# ATS_Unit.net
KiCad netlist of a schematic drawn in Altium Designer
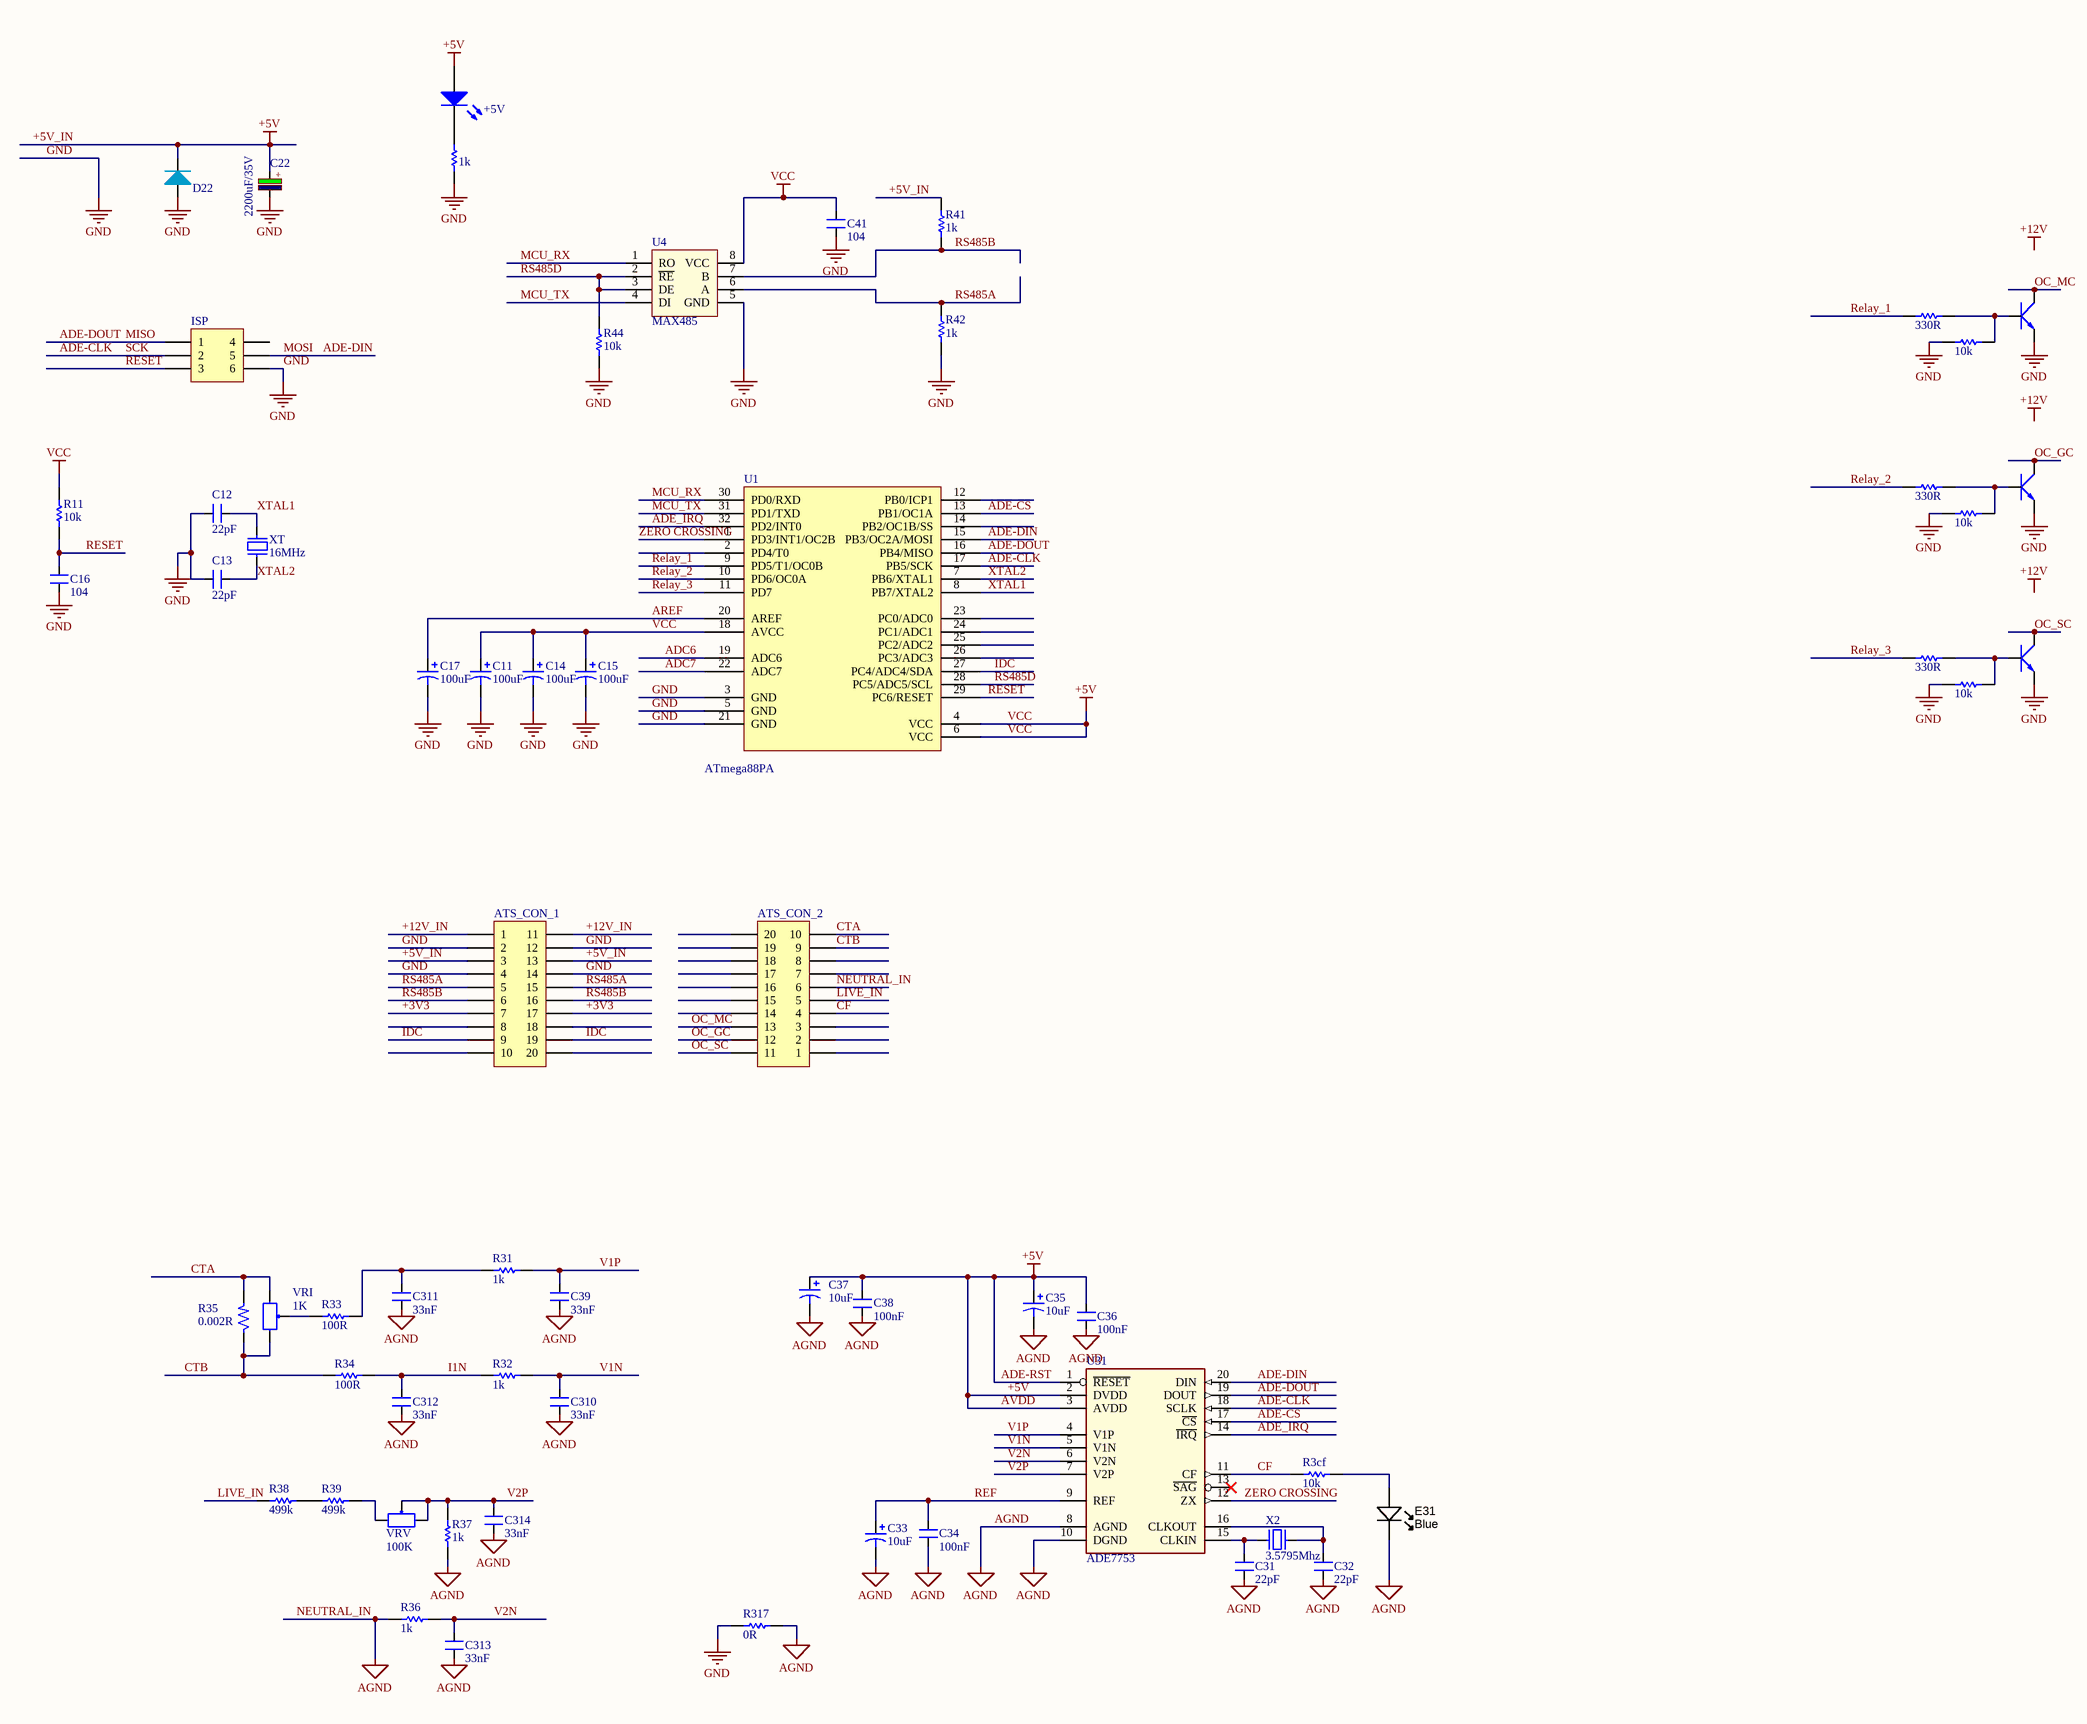
[diagram p0: ATS_Unit.SchDoc]

(export (version "E")
  (design (tool "Eeschema 10.0.6"))
  (components
    (comp (ref "+5V") (value "Led") (footprint "LED 5mm RED") (libsource (lib "Tuan") (part "Led")))
    (comp (ref "ATS_CON_1")
      (value "Header 10X2A")
      (footprint "OMC10")
      (description "Header, 10-Pin, Dual row")
      (fields (field (name "PUBLISHER") "Altium Limited"))
      (libsource (lib "Miscellaneous Connectors") (part "Header 10X2A"))
    )
    (comp (ref "ATS_CON_2")
      (value "Header 10X2A")
      (footprint "OMC10")
      (description "Header, 10-Pin, Dual row")
      (fields (field (name "PUBLISHER") "Altium Limited"))
      (libsource (lib "") (part "Header 10X2A_1"))
    )
    (comp (ref "C11")
      (value "100uF")
      (footprint "CAPC2012N_F")
      (fields (field (name "Comment") "Cap"))
      (libsource (lib "Tuan") (part "Cap"))
    )
    (comp (ref "C12")
      (value "22pF")
      (footprint "CAPC1608N")
      (fields (field (name "Comment") "CAP NP"))
      (libsource (lib "Tuan") (part "CAP NP"))
    )
    (comp (ref "C13")
      (value "22pF")
      (footprint "CAPC1608N")
      (fields (field (name "Comment") "CAP NP"))
      (libsource (lib "Tuan") (part "CAP NP"))
    )
    (comp (ref "C14")
      (value "100uF")
      (footprint "CAPC2012N_F")
      (fields (field (name "Comment") "Cap"))
      (libsource (lib "Tuan") (part "Cap"))
    )
    (comp (ref "C15")
      (value "100uF")
      (footprint "CAPC2012N_F")
      (fields (field (name "Comment") "Cap"))
      (libsource (lib "Tuan") (part "Cap"))
    )
    (comp (ref "C16")
      (value "104")
      (footprint "CAPC1608N")
      (fields (field (name "Comment") "CAP NP"))
      (libsource (lib "Tuan") (part "CAP NP"))
    )
    (comp (ref "C17")
      (value "100uF")
      (footprint "CAPC2012N_F")
      (fields (field (name "Comment") "Cap"))
      (libsource (lib "Tuan") (part "Cap"))
    )
    (comp (ref "C22")
      (value "2200uF/35V")
      (footprint "PBL - SMD Packages:CAP_ELEC_SIZE_G")
      (description "Cap 1000uF/16V - 220uF/50V")
      (libsource (lib "heromap") (part "CP4"))
    )
    (comp (ref "C31")
      (value "22pF")
      (footprint "CAPC1608N")
      (fields (field (name "Comment") "CAP NP"))
      (libsource (lib "ELS-PLC-2.0") (part "CAP NP"))
    )
    (comp (ref "C32")
      (value "22pF")
      (footprint "CAPC1608N")
      (fields (field (name "Comment") "CAP NP"))
      (libsource (lib "ELS-PLC-2.0") (part "CAP NP"))
    )
    (comp (ref "C33")
      (value "10uF")
      (footprint "CAPC2012N_F")
      (fields (field (name "Comment") "Cap"))
      (libsource (lib "Tuan") (part "Cap"))
    )
    (comp (ref "C34")
      (value "100nF")
      (footprint "CAPC1608N")
      (fields (field (name "Comment") "CAP NP"))
      (libsource (lib "ELS-PLC-2.0") (part "CAP NP"))
    )
    (comp (ref "C35")
      (value "10uF")
      (footprint "CAPC2012N_F")
      (fields (field (name "Comment") "Cap"))
      (libsource (lib "Tuan") (part "Cap"))
    )
    (comp (ref "C36")
      (value "100nF")
      (footprint "CAPC1608N")
      (fields (field (name "Comment") "CAP NP"))
      (libsource (lib "ELS-PLC-2.0") (part "CAP NP"))
    )
    (comp (ref "C37")
      (value "10uF")
      (footprint "CAPC2012N_F")
      (fields (field (name "Comment") "Cap"))
      (libsource (lib "Tuan") (part "Cap"))
    )
    (comp (ref "C38")
      (value "100nF")
      (footprint "CAPC1608N")
      (fields (field (name "Comment") "CAP NP"))
      (libsource (lib "ELS-PLC-2.0") (part "CAP NP"))
    )
    (comp (ref "C39")
      (value "33nF")
      (footprint "CAPC1608N")
      (fields (field (name "Comment") "CAP NP"))
      (libsource (lib "ELS-PLC-2.0") (part "CAP NP"))
    )
    (comp (ref "C41")
      (value "104")
      (footprint "CAPC2012N_F")
      (fields (field (name "Comment") "100nF/104"))
      (libsource (lib "Tuan") (part "CAP NP"))
    )
    (comp (ref "C310")
      (value "33nF")
      (footprint "CAPC1608N")
      (fields (field (name "Comment") "CAP NP"))
      (libsource (lib "ELS-PLC-2.0") (part "CAP NP"))
    )
    (comp (ref "C311")
      (value "33nF")
      (footprint "CAPC1608N")
      (fields (field (name "Comment") "CAP NP"))
      (libsource (lib "ELS-PLC-2.0") (part "CAP NP"))
    )
    (comp (ref "C312")
      (value "33nF")
      (footprint "CAPC1608N")
      (fields (field (name "Comment") "CAP NP"))
      (libsource (lib "ELS-PLC-2.0") (part "CAP NP"))
    )
    (comp (ref "C313")
      (value "33nF")
      (footprint "CAPC1608N")
      (fields (field (name "Comment") "CAP NP"))
      (libsource (lib "ELS-PLC-2.0") (part "CAP NP"))
    )
    (comp (ref "C314")
      (value "33nF")
      (footprint "CAPC1608N")
      (fields (field (name "Comment") "CAP NP"))
      (libsource (lib "ELS-PLC-2.0") (part "CAP NP"))
    )
    (comp (ref "D22") (value "Diode") (footprint "DO-214AC") (libsource (lib "Tuan") (part "Diode")))
    (comp (ref "E31")
      (value "Blue")
      (footprint "LED-0805-K")
      (description "LED 0805 SMD Blue 100mcd 470nm")
      (fields (field (name "COLOR") "Blue"))
      (libsource (lib "PBL - Light Sources") (part "LED_SMD_Blue_0805_100mcd"))
    )
    (comp (ref "ISP")
      (value "Header 3X2A")
      (footprint "HDR2X3_CEN")
      (description "Header, 3-Pin, Dual row")
      (fields (field (name "PUBLISHER") "Altium Limited"))
      (libsource (lib "Miscellaneous Connectors") (part "Header 3X2A"))
    )
    (comp (ref "Qo1")
      (value "C828")
      (footprint "SOT23 TOP")
      (description "Transistor C828 C1815....")
      (libsource (lib "Tuan") (part "NPN"))
    )
    (comp (ref "Qo2")
      (value "C828")
      (footprint "SOT23 TOP")
      (description "Transistor C828 C1815....")
      (libsource (lib "Tuan") (part "NPN"))
    )
    (comp (ref "Qo3")
      (value "C828")
      (footprint "SOT23 TOP")
      (description "Transistor C828 C1815....")
      (libsource (lib "Tuan") (part "NPN"))
    )
    (comp (ref "R3cf")
      (value "10k")
      (footprint "0603ESDA")
      (fields (field (name "Comment") "Res"))
      (libsource (lib "Tuan") (part "Res"))
    )
    (comp (ref "R11")
      (value "10k")
      (footprint "RESC1608N_ZERO")
      (fields (field (name "Comment") "Res"))
      (libsource (lib "Tuan") (part "Res"))
    )
    (comp (ref "R22")
      (value "1k")
      (footprint "RESC2012N_F")
      (fields (field (name "Comment") "Res_0805_1k"))
      (libsource (lib "Tuan") (part "Res"))
    )
    (comp (ref "R31")
      (value "1k")
      (footprint "0603ESDA")
      (fields (field (name "Comment") "Res"))
      (libsource (lib "Tuan") (part "Res"))
    )
    (comp (ref "R32")
      (value "1k")
      (footprint "0603ESDA")
      (fields (field (name "Comment") "Res"))
      (libsource (lib "Tuan") (part "Res"))
    )
    (comp (ref "R33")
      (value "100R")
      (footprint "0603ESDA")
      (fields (field (name "Comment") "Res"))
      (libsource (lib "Tuan") (part "Res"))
    )
    (comp (ref "R34")
      (value "100R")
      (footprint "0603ESDA")
      (fields (field (name "Comment") "Res"))
      (libsource (lib "Tuan") (part "Res"))
    )
    (comp (ref "R35")
      (value "0.002R")
      (footprint "RESC6332N")
      (description "Resistor 1/4W")
      (libsource (lib "syhaunguyen") (part "R"))
    )
    (comp (ref "R36")
      (value "1k")
      (footprint "0603ESDA")
      (fields (field (name "Comment") "Res"))
      (libsource (lib "Tuan") (part "Res"))
    )
    (comp (ref "R37")
      (value "1k")
      (footprint "0603ESDA")
      (fields (field (name "Comment") "Res"))
      (libsource (lib "Tuan") (part "Res"))
    )
    (comp (ref "R38")
      (value "499k")
      (footprint "RESC2012N_F")
      (fields (field (name "Comment") "Res"))
      (libsource (lib "Tuan") (part "Res"))
    )
    (comp (ref "R39")
      (value "499k")
      (footprint "RESC2012N_F")
      (fields (field (name "Comment") "Res"))
      (libsource (lib "Tuan") (part "Res"))
    )
    (comp (ref "R41")
      (value "1k")
      (footprint "RESC1608N_ZERO")
      (description "Tro dan")
      (libsource (lib "GPS_Clock_v12") (part "Res"))
    )
    (comp (ref "R42")
      (value "1k")
      (footprint "RESC1608N_ZERO")
      (description "Tro dan")
      (libsource (lib "GPS_Clock_v12") (part "Res"))
    )
    (comp (ref "R44")
      (value "10k")
      (footprint "RESC1608N_ZERO")
      (description "Tro dan")
      (fields (field (name "Comment") "330R"))
      (libsource (lib "GPS_Clock_v12") (part "Res"))
    )
    (comp (ref "R317")
      (value "0R")
      (footprint "RESC2012N_F")
      (fields (field (name "Comment") "Res"))
      (libsource (lib "Tuan") (part "Res"))
    )
    (comp (ref "Rp1")
      (value "10k")
      (footprint "RESC1608N_ZERO")
      (fields (field (name "Comment") "Res"))
      (libsource (lib "Tuan") (part "Res"))
    )
    (comp (ref "Rp2")
      (value "10k")
      (footprint "RESC1608N_ZERO")
      (fields (field (name "Comment") "Res"))
      (libsource (lib "Tuan") (part "Res"))
    )
    (comp (ref "Rp3")
      (value "10k")
      (footprint "RESC1608N_ZERO")
      (fields (field (name "Comment") "Res"))
      (libsource (lib "Tuan") (part "Res"))
    )
    (comp (ref "Rr1")
      (value "330R")
      (footprint "RESC1608N_ZERO")
      (fields (field (name "Comment") "Res"))
      (libsource (lib "Tuan") (part "Res"))
    )
    (comp (ref "Rr2")
      (value "330R")
      (footprint "RESC1608N_ZERO")
      (fields (field (name "Comment") "Res"))
      (libsource (lib "Tuan") (part "Res"))
    )
    (comp (ref "Rr3")
      (value "330R")
      (footprint "RESC1608N_ZERO")
      (fields (field (name "Comment") "Res"))
      (libsource (lib "Tuan") (part "Res"))
    )
    (comp (ref "U1")
      (value "ATmega88PA")
      (footprint "32PIN")
      (description "ATmega48/168/328")
      (libsource (lib "Tuan") (part "ATmega48/168/328"))
    )
    (comp (ref "U4")
      (value "MAX485")
      (footprint "SO-8")
      (description "RS232 - RS485 (Same sn75176)")
      (libsource (lib "heromap") (part "MAX485"))
    )
    (comp (ref "U31")
      (value "ADE7753")
      (footprint "TSSOP-20")
      (description "Single-Phase Multifunction Metering IC with di/dt Sensor Interface")
      (libsource (lib "heromap") (part "ADE7753"))
    )
    (comp (ref "VRI")
      (value "1K")
      (footprint "heromap:VR1")
      (description "Var Resistor")
      (libsource (lib "heromap") (part "VR"))
    )
    (comp (ref "VRV")
      (value "100K")
      (footprint "heromap:VR1")
      (description "Var Resistor")
      (libsource (lib "heromap") (part "VR"))
    )
    (comp (ref "X2")
      (value "3.5795Mhz")
      (footprint "heromap:XT2")
      (description "Crystal For all Crystal 2pin.")
      (libsource (lib "heromap") (part "XT2"))
    )
    (comp (ref "XT") (value "16MHz") (footprint "XT2") (libsource (lib "Tuan") (part "Crystal")))
  )
  (nets
    (net (code "1") (name "+5V") (class "Default")
      (node (ref "+5V") (pin "1") (pinfunction "A_1") (pintype "passive"))
      (node (ref "ATS_CON_1") (pin "13") (pinfunction "13_13") (pintype "passive"))
      (node (ref "ATS_CON_1") (pin "3") (pinfunction "3_3") (pintype "passive"))
      (node (ref "C11") (pin "1") (pinfunction "1_1") (pintype "passive"))
      (node (ref "C14") (pin "1") (pinfunction "1_1") (pintype "passive"))
      (node (ref "C15") (pin "1") (pinfunction "1_1") (pintype "passive"))
      (node (ref "C22") (pin "1") (pinfunction "1_1") (pintype "passive"))
      (node (ref "C35") (pin "1") (pinfunction "1_1") (pintype "passive"))
      (node (ref "C36") (pin "2") (pinfunction "2_2") (pintype "passive"))
      (node (ref "C37") (pin "1") (pinfunction "1_1") (pintype "passive"))
      (node (ref "C38") (pin "2") (pinfunction "2_2") (pintype "passive"))
      (node (ref "C41") (pin "2") (pinfunction "2_2") (pintype "passive"))
      (node (ref "D22") (pin "2") (pinfunction "K_2") (pintype "passive"))
      (node (ref "R11") (pin "2") (pinfunction "2_2") (pintype "passive"))
      (node (ref "R41") (pin "2") (pinfunction "2_2") (pintype "passive"))
      (node (ref "U1") (pin "18") (pinfunction "AVCC_18") (pintype "passive"))
      (node (ref "U1") (pin "4") (pinfunction "VCC_4") (pintype "passive"))
      (node (ref "U1") (pin "6") (pinfunction "VCC_6") (pintype "passive"))
      (node (ref "U31") (pin "1") (pinfunction "~{RESET}_1") (pintype "passive"))
      (node (ref "U31") (pin "2") (pinfunction "DVDD_2") (pintype "passive"))
      (node (ref "U31") (pin "3") (pinfunction "AVDD_3") (pintype "passive"))
      (node (ref "U4") (pin "8") (pinfunction "VCC_8") (pintype "passive"))
    )
    (net (code "3") (name "/+3V3") (class "Default")
      (node (ref "ATS_CON_1") (pin "17") (pinfunction "17_17") (pintype "passive"))
      (node (ref "ATS_CON_1") (pin "7") (pinfunction "7_7") (pintype "passive"))
    )
    (net (code "4") (name "/+12V_IN") (class "Default")
      (node (ref "ATS_CON_1") (pin "1") (pinfunction "1_1") (pintype "passive"))
      (node (ref "ATS_CON_1") (pin "11") (pinfunction "11_11") (pintype "passive"))
    )
    (net (code "5") (name "/ADC6") (class "Default")
      (node (ref "U1") (pin "19") (pinfunction "ADC6_19") (pintype "passive"))
    )
    (net (code "6") (name "/ADC7") (class "Default")
      (node (ref "U1") (pin "22") (pinfunction "ADC7_22") (pintype "passive"))
    )
    (net (code "7") (name "/ADE-CLK") (class "Default")
      (node (ref "ISP") (pin "2") (pinfunction "2_2") (pintype "passive"))
      (node (ref "U1") (pin "17") (pinfunction "PB5/SCK_17") (pintype "passive"))
      (node (ref "U31") (pin "18") (pinfunction "SCLK_18") (pintype "input"))
    )
    (net (code "8") (name "/ADE-CS") (class "Default")
      (node (ref "U1") (pin "13") (pinfunction "PB1/OC1A_13") (pintype "passive"))
      (node (ref "U31") (pin "17") (pinfunction "~{CS}_17") (pintype "input"))
    )
    (net (code "9") (name "/ADE-DIN") (class "Default")
      (node (ref "ISP") (pin "5") (pinfunction "5_5") (pintype "passive"))
      (node (ref "U1") (pin "15") (pinfunction "PB3/OC2A/MOSI_15") (pintype "passive"))
      (node (ref "U31") (pin "20") (pinfunction "DIN_20") (pintype "input"))
    )
    (net (code "10") (name "/ADE-DOUT") (class "Default")
      (node (ref "ISP") (pin "1") (pinfunction "1_1") (pintype "passive"))
      (node (ref "U1") (pin "16") (pinfunction "PB4/MISO_16") (pintype "passive"))
      (node (ref "U31") (pin "19") (pinfunction "DOUT_19") (pintype "output"))
    )
    (net (code "11") (name "/ADE_IRQ") (class "Default")
      (node (ref "U1") (pin "32") (pinfunction "PD2/INT0_32") (pintype "passive"))
      (node (ref "U31") (pin "14") (pinfunction "~{IRQ}_14") (pintype "output"))
    )
    (net (code "12") (name "/AREF") (class "Default")
      (node (ref "C17") (pin "1") (pinfunction "1_1") (pintype "passive"))
      (node (ref "U1") (pin "20") (pinfunction "AREF_20") (pintype "passive"))
    )
    (net (code "13") (name "/CF") (class "Default")
      (node (ref "ATS_CON_2") (pin "4") (pinfunction "4_4") (pintype "passive"))
      (node (ref "R3cf") (pin "1") (pinfunction "1_1") (pintype "passive"))
      (node (ref "U31") (pin "11") (pinfunction "CF_11") (pintype "output"))
    )
    (net (code "14") (name "/CTA") (class "Default")
      (node (ref "ATS_CON_2") (pin "10") (pinfunction "10_10") (pintype "passive"))
      (node (ref "R35") (pin "2") (pinfunction "2_2") (pintype "passive"))
      (node (ref "VRI") (pin "1") (pinfunction "1_1") (pintype "passive"))
    )
    (net (code "15") (name "/CTB") (class "Default")
      (node (ref "ATS_CON_2") (pin "9") (pinfunction "9_9") (pintype "passive"))
      (node (ref "R34") (pin "1") (pinfunction "1_1") (pintype "passive"))
      (node (ref "R35") (pin "1") (pinfunction "1_1") (pintype "passive"))
      (node (ref "VRI") (pin "3") (pinfunction "3_3") (pintype "passive"))
    )
    (net (code "16") (name "/I1N") (class "Default")
      (node (ref "C312") (pin "2") (pinfunction "2_2") (pintype "passive"))
      (node (ref "R32") (pin "1") (pinfunction "1_1") (pintype "passive"))
      (node (ref "R34") (pin "2") (pinfunction "2_2") (pintype "passive"))
    )
    (net (code "17") (name "/IDC") (class "Default")
      (node (ref "ATS_CON_1") (pin "19") (pinfunction "19_19") (pintype "passive"))
      (node (ref "ATS_CON_1") (pin "9") (pinfunction "9_9") (pintype "passive"))
      (node (ref "U1") (pin "27") (pinfunction "PC4/ADC4/SDA_27") (pintype "passive"))
    )
    (net (code "18") (name "/LIVE_IN") (class "Default")
      (node (ref "ATS_CON_2") (pin "5") (pinfunction "5_5") (pintype "passive"))
      (node (ref "R38") (pin "1") (pinfunction "1_1") (pintype "passive"))
    )
    (net (code "19") (name "/MCU_RX") (class "Default")
      (node (ref "U1") (pin "30") (pinfunction "PD0/RXD_30") (pintype "passive"))
      (node (ref "U4") (pin "1") (pinfunction "RO_1") (pintype "passive"))
    )
    (net (code "20") (name "/MCU_TX") (class "Default")
      (node (ref "U1") (pin "31") (pinfunction "PD1/TXD_31") (pintype "passive"))
      (node (ref "U4") (pin "4") (pinfunction "DI_4") (pintype "passive"))
    )
    (net (code "21") (name "/OC_GC") (class "Default")
      (node (ref "ATS_CON_2") (pin "12") (pinfunction "12_12") (pintype "passive"))
      (node (ref "Qo2") (pin "2") (pinfunction "C_2") (pintype "passive"))
    )
    (net (code "22") (name "/OC_MC") (class "Default")
      (node (ref "ATS_CON_2") (pin "13") (pinfunction "13_13") (pintype "passive"))
      (node (ref "Qo1") (pin "2") (pinfunction "C_2") (pintype "passive"))
    )
    (net (code "23") (name "/OC_SC") (class "Default")
      (node (ref "ATS_CON_2") (pin "11") (pinfunction "11_11") (pintype "passive"))
      (node (ref "Qo3") (pin "2") (pinfunction "C_2") (pintype "passive"))
    )
    (net (code "24") (name "/REF") (class "Default")
      (node (ref "C33") (pin "1") (pinfunction "1_1") (pintype "passive"))
      (node (ref "C34") (pin "2") (pinfunction "2_2") (pintype "passive"))
      (node (ref "U31") (pin "9") (pinfunction "REF_9") (pintype "passive"))
    )
    (net (code "25") (name "/RESET") (class "Default")
      (node (ref "C16") (pin "2") (pinfunction "2_2") (pintype "passive"))
      (node (ref "ISP") (pin "3") (pinfunction "3_3") (pintype "passive"))
      (node (ref "R11") (pin "1") (pinfunction "1_1") (pintype "passive"))
      (node (ref "U1") (pin "29") (pinfunction "PC6/RESET_29") (pintype "passive"))
    )
    (net (code "26") (name "/RS485A") (class "Default")
      (node (ref "ATS_CON_1") (pin "15") (pinfunction "15_15") (pintype "passive"))
      (node (ref "ATS_CON_1") (pin "5") (pinfunction "5_5") (pintype "passive"))
      (node (ref "R42") (pin "2") (pinfunction "2_2") (pintype "passive"))
      (node (ref "U4") (pin "6") (pinfunction "A_6") (pintype "passive"))
    )
    (net (code "27") (name "/RS485B") (class "Default")
      (node (ref "ATS_CON_1") (pin "16") (pinfunction "16_16") (pintype "passive"))
      (node (ref "ATS_CON_1") (pin "6") (pinfunction "6_6") (pintype "passive"))
      (node (ref "R41") (pin "1") (pinfunction "1_1") (pintype "passive"))
      (node (ref "U4") (pin "7") (pinfunction "B_7") (pintype "passive"))
    )
    (net (code "28") (name "/RS485D") (class "Default")
      (node (ref "R44") (pin "2") (pinfunction "2_2") (pintype "passive"))
      (node (ref "U1") (pin "28") (pinfunction "PC5/ADC5/SCL_28") (pintype "passive"))
      (node (ref "U4") (pin "2") (pinfunction "~{RE}_2") (pintype "passive"))
      (node (ref "U4") (pin "3") (pinfunction "DE_3") (pintype "passive"))
    )
    (net (code "29") (name "/Relay_1") (class "Default")
      (node (ref "Rr1") (pin "1") (pinfunction "1_1") (pintype "passive"))
      (node (ref "U1") (pin "9") (pinfunction "PD5/T1/OC0B_9") (pintype "passive"))
    )
    (net (code "30") (name "/Relay_2") (class "Default")
      (node (ref "Rr2") (pin "1") (pinfunction "1_1") (pintype "passive"))
      (node (ref "U1") (pin "10") (pinfunction "PD6/OC0A_10") (pintype "passive"))
    )
    (net (code "31") (name "/Relay_3") (class "Default")
      (node (ref "Rr3") (pin "1") (pinfunction "1_1") (pintype "passive"))
      (node (ref "U1") (pin "11") (pinfunction "PD7_11") (pintype "passive"))
    )
    (net (code "32") (name "/V1N") (class "Default")
      (node (ref "C310") (pin "2") (pinfunction "2_2") (pintype "passive"))
      (node (ref "R32") (pin "2") (pinfunction "2_2") (pintype "passive"))
      (node (ref "U31") (pin "5") (pinfunction "V1N_5") (pintype "passive"))
    )
    (net (code "33") (name "/V1P") (class "Default")
      (node (ref "C39") (pin "2") (pinfunction "2_2") (pintype "passive"))
      (node (ref "R31") (pin "2") (pinfunction "2_2") (pintype "passive"))
      (node (ref "U31") (pin "4") (pinfunction "V1P_4") (pintype "passive"))
    )
    (net (code "34") (name "/V2N") (class "Default")
      (node (ref "C313") (pin "2") (pinfunction "2_2") (pintype "passive"))
      (node (ref "R36") (pin "2") (pinfunction "2_2") (pintype "passive"))
      (node (ref "U31") (pin "6") (pinfunction "V2N_6") (pintype "passive"))
    )
    (net (code "35") (name "/V2P") (class "Default")
      (node (ref "C314") (pin "2") (pinfunction "2_2") (pintype "passive"))
      (node (ref "R37") (pin "2") (pinfunction "2_2") (pintype "passive"))
      (node (ref "U31") (pin "7") (pinfunction "V2P_7") (pintype "passive"))
      (node (ref "VRV") (pin "2") (pinfunction "2_2") (pintype "passive"))
      (node (ref "VRV") (pin "3") (pinfunction "3_3") (pintype "passive"))
    )
    (net (code "36") (name "/XTAL1") (class "Default")
      (node (ref "C12") (pin "1") (pinfunction "1_1") (pintype "passive"))
      (node (ref "U1") (pin "8") (pinfunction "PB7/XTAL2_8") (pintype "passive"))
      (node (ref "XT") (pin "2") (pinfunction "2_2") (pintype "passive"))
    )
    (net (code "37") (name "/XTAL2") (class "Default")
      (node (ref "C13") (pin "1") (pinfunction "1_1") (pintype "passive"))
      (node (ref "U1") (pin "7") (pinfunction "PB6/XTAL1_7") (pintype "passive"))
      (node (ref "XT") (pin "1") (pinfunction "1_1") (pintype "passive"))
    )
    (net (code "38") (name "/ZERO CROSSING") (class "Default")
      (node (ref "U1") (pin "1") (pinfunction "PD3/INT1/OC2B_1") (pintype "passive"))
      (node (ref "U31") (pin "12") (pinfunction "ZX_12") (pintype "output"))
    )
    (net (code "39") (name "AGND") (class "Default")
      (node (ref "ATS_CON_2") (pin "6") (pinfunction "6_6") (pintype "passive"))
      (node (ref "C31") (pin "1") (pinfunction "1_1") (pintype "passive"))
      (node (ref "C310") (pin "1") (pinfunction "1_1") (pintype "passive"))
      (node (ref "C311") (pin "1") (pinfunction "1_1") (pintype "passive"))
      (node (ref "C312") (pin "1") (pinfunction "1_1") (pintype "passive"))
      (node (ref "C313") (pin "1") (pinfunction "1_1") (pintype "passive"))
      (node (ref "C314") (pin "1") (pinfunction "1_1") (pintype "passive"))
      (node (ref "C32") (pin "1") (pinfunction "1_1") (pintype "passive"))
      (node (ref "C33") (pin "2") (pinfunction "2_2") (pintype "passive"))
      (node (ref "C34") (pin "1") (pinfunction "1_1") (pintype "passive"))
      (node (ref "C35") (pin "2") (pinfunction "2_2") (pintype "passive"))
      (node (ref "C36") (pin "1") (pinfunction "1_1") (pintype "passive"))
      (node (ref "C37") (pin "2") (pinfunction "2_2") (pintype "passive"))
      (node (ref "C38") (pin "1") (pinfunction "1_1") (pintype "passive"))
      (node (ref "C39") (pin "1") (pinfunction "1_1") (pintype "passive"))
      (node (ref "E31") (pin "K") (pinfunction "K_K") (pintype "passive"))
      (node (ref "R317") (pin "2") (pinfunction "2_2") (pintype "passive"))
      (node (ref "R36") (pin "1") (pinfunction "1_1") (pintype "passive"))
      (node (ref "R37") (pin "1") (pinfunction "1_1") (pintype "passive"))
      (node (ref "U31") (pin "10") (pinfunction "DGND_10") (pintype "passive"))
      (node (ref "U31") (pin "8") (pinfunction "AGND_8") (pintype "passive"))
    )
    (net (code "40") (name "GND") (class "Default")
      (node (ref "ATS_CON_1") (pin "12") (pinfunction "12_12") (pintype "passive"))
      (node (ref "ATS_CON_1") (pin "14") (pinfunction "14_14") (pintype "passive"))
      (node (ref "ATS_CON_1") (pin "2") (pinfunction "2_2") (pintype "passive"))
      (node (ref "ATS_CON_1") (pin "4") (pinfunction "4_4") (pintype "passive"))
      (node (ref "C11") (pin "2") (pinfunction "2_2") (pintype "passive"))
      (node (ref "C12") (pin "2") (pinfunction "2_2") (pintype "passive"))
      (node (ref "C13") (pin "2") (pinfunction "2_2") (pintype "passive"))
      (node (ref "C14") (pin "2") (pinfunction "2_2") (pintype "passive"))
      (node (ref "C15") (pin "2") (pinfunction "2_2") (pintype "passive"))
      (node (ref "C16") (pin "1") (pinfunction "1_1") (pintype "passive"))
      (node (ref "C17") (pin "2") (pinfunction "2_2") (pintype "passive"))
      (node (ref "C22") (pin "2") (pinfunction "2_2") (pintype "passive"))
      (node (ref "C41") (pin "1") (pinfunction "1_1") (pintype "passive"))
      (node (ref "D22") (pin "1") (pinfunction "A_1") (pintype "passive"))
      (node (ref "ISP") (pin "6") (pinfunction "6_6") (pintype "passive"))
      (node (ref "Qo1") (pin "3") (pinfunction "E_3") (pintype "passive"))
      (node (ref "Qo2") (pin "3") (pinfunction "E_3") (pintype "passive"))
      (node (ref "Qo3") (pin "3") (pinfunction "E_3") (pintype "passive"))
      (node (ref "R22") (pin "2") (pinfunction "2_2") (pintype "passive"))
      (node (ref "R317") (pin "1") (pinfunction "1_1") (pintype "passive"))
      (node (ref "R42") (pin "1") (pinfunction "1_1") (pintype "passive"))
      (node (ref "R44") (pin "1") (pinfunction "1_1") (pintype "passive"))
      (node (ref "Rp1") (pin "1") (pinfunction "1_1") (pintype "passive"))
      (node (ref "Rp2") (pin "1") (pinfunction "1_1") (pintype "passive"))
      (node (ref "Rp3") (pin "1") (pinfunction "1_1") (pintype "passive"))
      (node (ref "U1") (pin "21") (pinfunction "GND_21") (pintype "power_in"))
      (node (ref "U1") (pin "3") (pinfunction "GND_3") (pintype "power_in"))
      (node (ref "U1") (pin "5") (pinfunction "GND_5") (pintype "power_in"))
      (node (ref "U4") (pin "5") (pinfunction "GND_5") (pintype "passive"))
    )
    (net (code "41") (name "Net-(+5V-K)") (class "Default")
      (node (ref "+5V") (pin "2") (pinfunction "K_2") (pintype "passive"))
      (node (ref "R22") (pin "1") (pinfunction "1_1") (pintype "passive"))
    )
    (net (code "42") (name "Net-(C311-Pad2)") (class "Default")
      (node (ref "C311") (pin "2") (pinfunction "2_2") (pintype "passive"))
      (node (ref "R31") (pin "1") (pinfunction "1_1") (pintype "passive"))
      (node (ref "R33") (pin "2") (pinfunction "2_2") (pintype "passive"))
    )
    (net (code "43") (name "Net-(E31-PadA)") (class "Default")
      (node (ref "E31") (pin "A") (pinfunction "A_A") (pintype "passive"))
      (node (ref "R3cf") (pin "2") (pinfunction "2_2") (pintype "passive"))
    )
    (net (code "44") (name "Net-(Qo1-B)") (class "Default")
      (node (ref "Qo1") (pin "1") (pinfunction "B_1") (pintype "passive"))
      (node (ref "Rp1") (pin "2") (pinfunction "2_2") (pintype "passive"))
      (node (ref "Rr1") (pin "2") (pinfunction "2_2") (pintype "passive"))
    )
    (net (code "45") (name "Net-(Qo2-B)") (class "Default")
      (node (ref "Qo2") (pin "1") (pinfunction "B_1") (pintype "passive"))
      (node (ref "Rp2") (pin "2") (pinfunction "2_2") (pintype "passive"))
      (node (ref "Rr2") (pin "2") (pinfunction "2_2") (pintype "passive"))
    )
    (net (code "46") (name "Net-(Qo3-B)") (class "Default")
      (node (ref "Qo3") (pin "1") (pinfunction "B_1") (pintype "passive"))
      (node (ref "Rp3") (pin "2") (pinfunction "2_2") (pintype "passive"))
      (node (ref "Rr3") (pin "2") (pinfunction "2_2") (pintype "passive"))
    )
    (net (code "47") (name "Net-(R33-Pad1)") (class "Default")
      (node (ref "R33") (pin "1") (pinfunction "1_1") (pintype "passive"))
      (node (ref "VRI") (pin "2") (pinfunction "2_2") (pintype "passive"))
    )
    (net (code "48") (name "Net-(R38-Pad2)") (class "Default")
      (node (ref "R38") (pin "2") (pinfunction "2_2") (pintype "passive"))
      (node (ref "R39") (pin "1") (pinfunction "1_1") (pintype "passive"))
    )
    (net (code "49") (name "Net-(R39-Pad2)") (class "Default")
      (node (ref "R39") (pin "2") (pinfunction "2_2") (pintype "passive"))
      (node (ref "VRV") (pin "1") (pinfunction "1_1") (pintype "passive"))
    )
    (net (code "50") (name "Net-(U31-CLKIN)") (class "Default")
      (node (ref "C31") (pin "2") (pinfunction "2_2") (pintype "passive"))
      (node (ref "U31") (pin "15") (pinfunction "CLKIN_15") (pintype "passive"))
      (node (ref "X2") (pin "2") (pinfunction "2_2") (pintype "passive"))
    )
    (net (code "51") (name "Net-(U31-CLKOUT)") (class "Default")
      (node (ref "C32") (pin "2") (pinfunction "2_2") (pintype "passive"))
      (node (ref "U31") (pin "16") (pinfunction "CLKOUT_16") (pintype "passive"))
      (node (ref "X2") (pin "1") (pinfunction "1_1") (pintype "passive"))
    )
    (net (code "52") (name "unconnected-(ATS_CON_1-Pad8)") (class "Default")
      (node (ref "ATS_CON_1") (pin "8") (pinfunction "8_8") (pintype "passive"))
    )
    (net (code "53") (name "unconnected-(ATS_CON_1-Pad10)") (class "Default")
      (node (ref "ATS_CON_1") (pin "10") (pinfunction "10_10") (pintype "passive"))
    )
    (net (code "54") (name "unconnected-(ATS_CON_1-Pad18)") (class "Default")
      (node (ref "ATS_CON_1") (pin "18") (pinfunction "18_18") (pintype "passive"))
    )
    (net (code "55") (name "unconnected-(ATS_CON_1-Pad20)") (class "Default")
      (node (ref "ATS_CON_1") (pin "20") (pinfunction "20_20") (pintype "passive"))
    )
    (net (code "56") (name "unconnected-(ATS_CON_2-Pad1)") (class "Default")
      (node (ref "ATS_CON_2") (pin "1") (pinfunction "1_1") (pintype "passive"))
    )
    (net (code "57") (name "unconnected-(ATS_CON_2-Pad2)") (class "Default")
      (node (ref "ATS_CON_2") (pin "2") (pinfunction "2_2") (pintype "passive"))
    )
    (net (code "58") (name "unconnected-(ATS_CON_2-Pad3)") (class "Default")
      (node (ref "ATS_CON_2") (pin "3") (pinfunction "3_3") (pintype "passive"))
    )
    (net (code "59") (name "unconnected-(ATS_CON_2-Pad7)") (class "Default")
      (node (ref "ATS_CON_2") (pin "7") (pinfunction "7_7") (pintype "passive"))
    )
    (net (code "60") (name "unconnected-(ATS_CON_2-Pad8)") (class "Default")
      (node (ref "ATS_CON_2") (pin "8") (pinfunction "8_8") (pintype "passive"))
    )
    (net (code "61") (name "unconnected-(ATS_CON_2-Pad14)") (class "Default")
      (node (ref "ATS_CON_2") (pin "14") (pinfunction "14_14") (pintype "passive"))
    )
    (net (code "62") (name "unconnected-(ATS_CON_2-Pad15)") (class "Default")
      (node (ref "ATS_CON_2") (pin "15") (pinfunction "15_15") (pintype "passive"))
    )
    (net (code "63") (name "unconnected-(ATS_CON_2-Pad16)") (class "Default")
      (node (ref "ATS_CON_2") (pin "16") (pinfunction "16_16") (pintype "passive"))
    )
    (net (code "64") (name "unconnected-(ATS_CON_2-Pad17)") (class "Default")
      (node (ref "ATS_CON_2") (pin "17") (pinfunction "17_17") (pintype "passive"))
    )
    (net (code "65") (name "unconnected-(ATS_CON_2-Pad18)") (class "Default")
      (node (ref "ATS_CON_2") (pin "18") (pinfunction "18_18") (pintype "passive"))
    )
    (net (code "66") (name "unconnected-(ATS_CON_2-Pad19)") (class "Default")
      (node (ref "ATS_CON_2") (pin "19") (pinfunction "19_19") (pintype "passive"))
    )
    (net (code "67") (name "unconnected-(ATS_CON_2-Pad20)") (class "Default")
      (node (ref "ATS_CON_2") (pin "20") (pinfunction "20_20") (pintype "passive"))
    )
    (net (code "68") (name "unconnected-(ISP-Pad4)") (class "Default")
      (node (ref "ISP") (pin "4") (pinfunction "4_4") (pintype "passive"))
    )
    (net (code "69") (name "unconnected-(U1-PB0{slash}ICP1-Pad12)") (class "Default")
      (node (ref "U1") (pin "12") (pinfunction "PB0/ICP1_12") (pintype "passive"))
    )
    (net (code "70") (name "unconnected-(U1-PB2{slash}OC1B{slash}SS-Pad14)") (class "Default")
      (node (ref "U1") (pin "14") (pinfunction "PB2/OC1B/SS_14") (pintype "passive"))
    )
    (net (code "71") (name "unconnected-(U1-PC0{slash}ADC0-Pad23)") (class "Default")
      (node (ref "U1") (pin "23") (pinfunction "PC0/ADC0_23") (pintype "passive"))
    )
    (net (code "72") (name "unconnected-(U1-PC1{slash}ADC1-Pad24)") (class "Default")
      (node (ref "U1") (pin "24") (pinfunction "PC1/ADC1_24") (pintype "passive"))
    )
    (net (code "73") (name "unconnected-(U1-PC2{slash}ADC2-Pad25)") (class "Default")
      (node (ref "U1") (pin "25") (pinfunction "PC2/ADC2_25") (pintype "passive"))
    )
    (net (code "74") (name "unconnected-(U1-PC3{slash}ADC3-Pad26)") (class "Default")
      (node (ref "U1") (pin "26") (pinfunction "PC3/ADC3_26") (pintype "passive"))
    )
    (net (code "75") (name "unconnected-(U1-PD4{slash}T0-Pad2)") (class "Default")
      (node (ref "U1") (pin "2") (pinfunction "PD4/T0_2") (pintype "passive"))
    )
    (net (code "76") (name "unconnected-(U31-~{SAG}-Pad13)") (class "Default")
      (node (ref "U31") (pin "13") (pinfunction "~{SAG}_13") (pintype "passive+no_connect"))
    )
  )
)
